# callisto_schematics_analog.net
KiCad netlist of a schematic drawn in Altium Designer
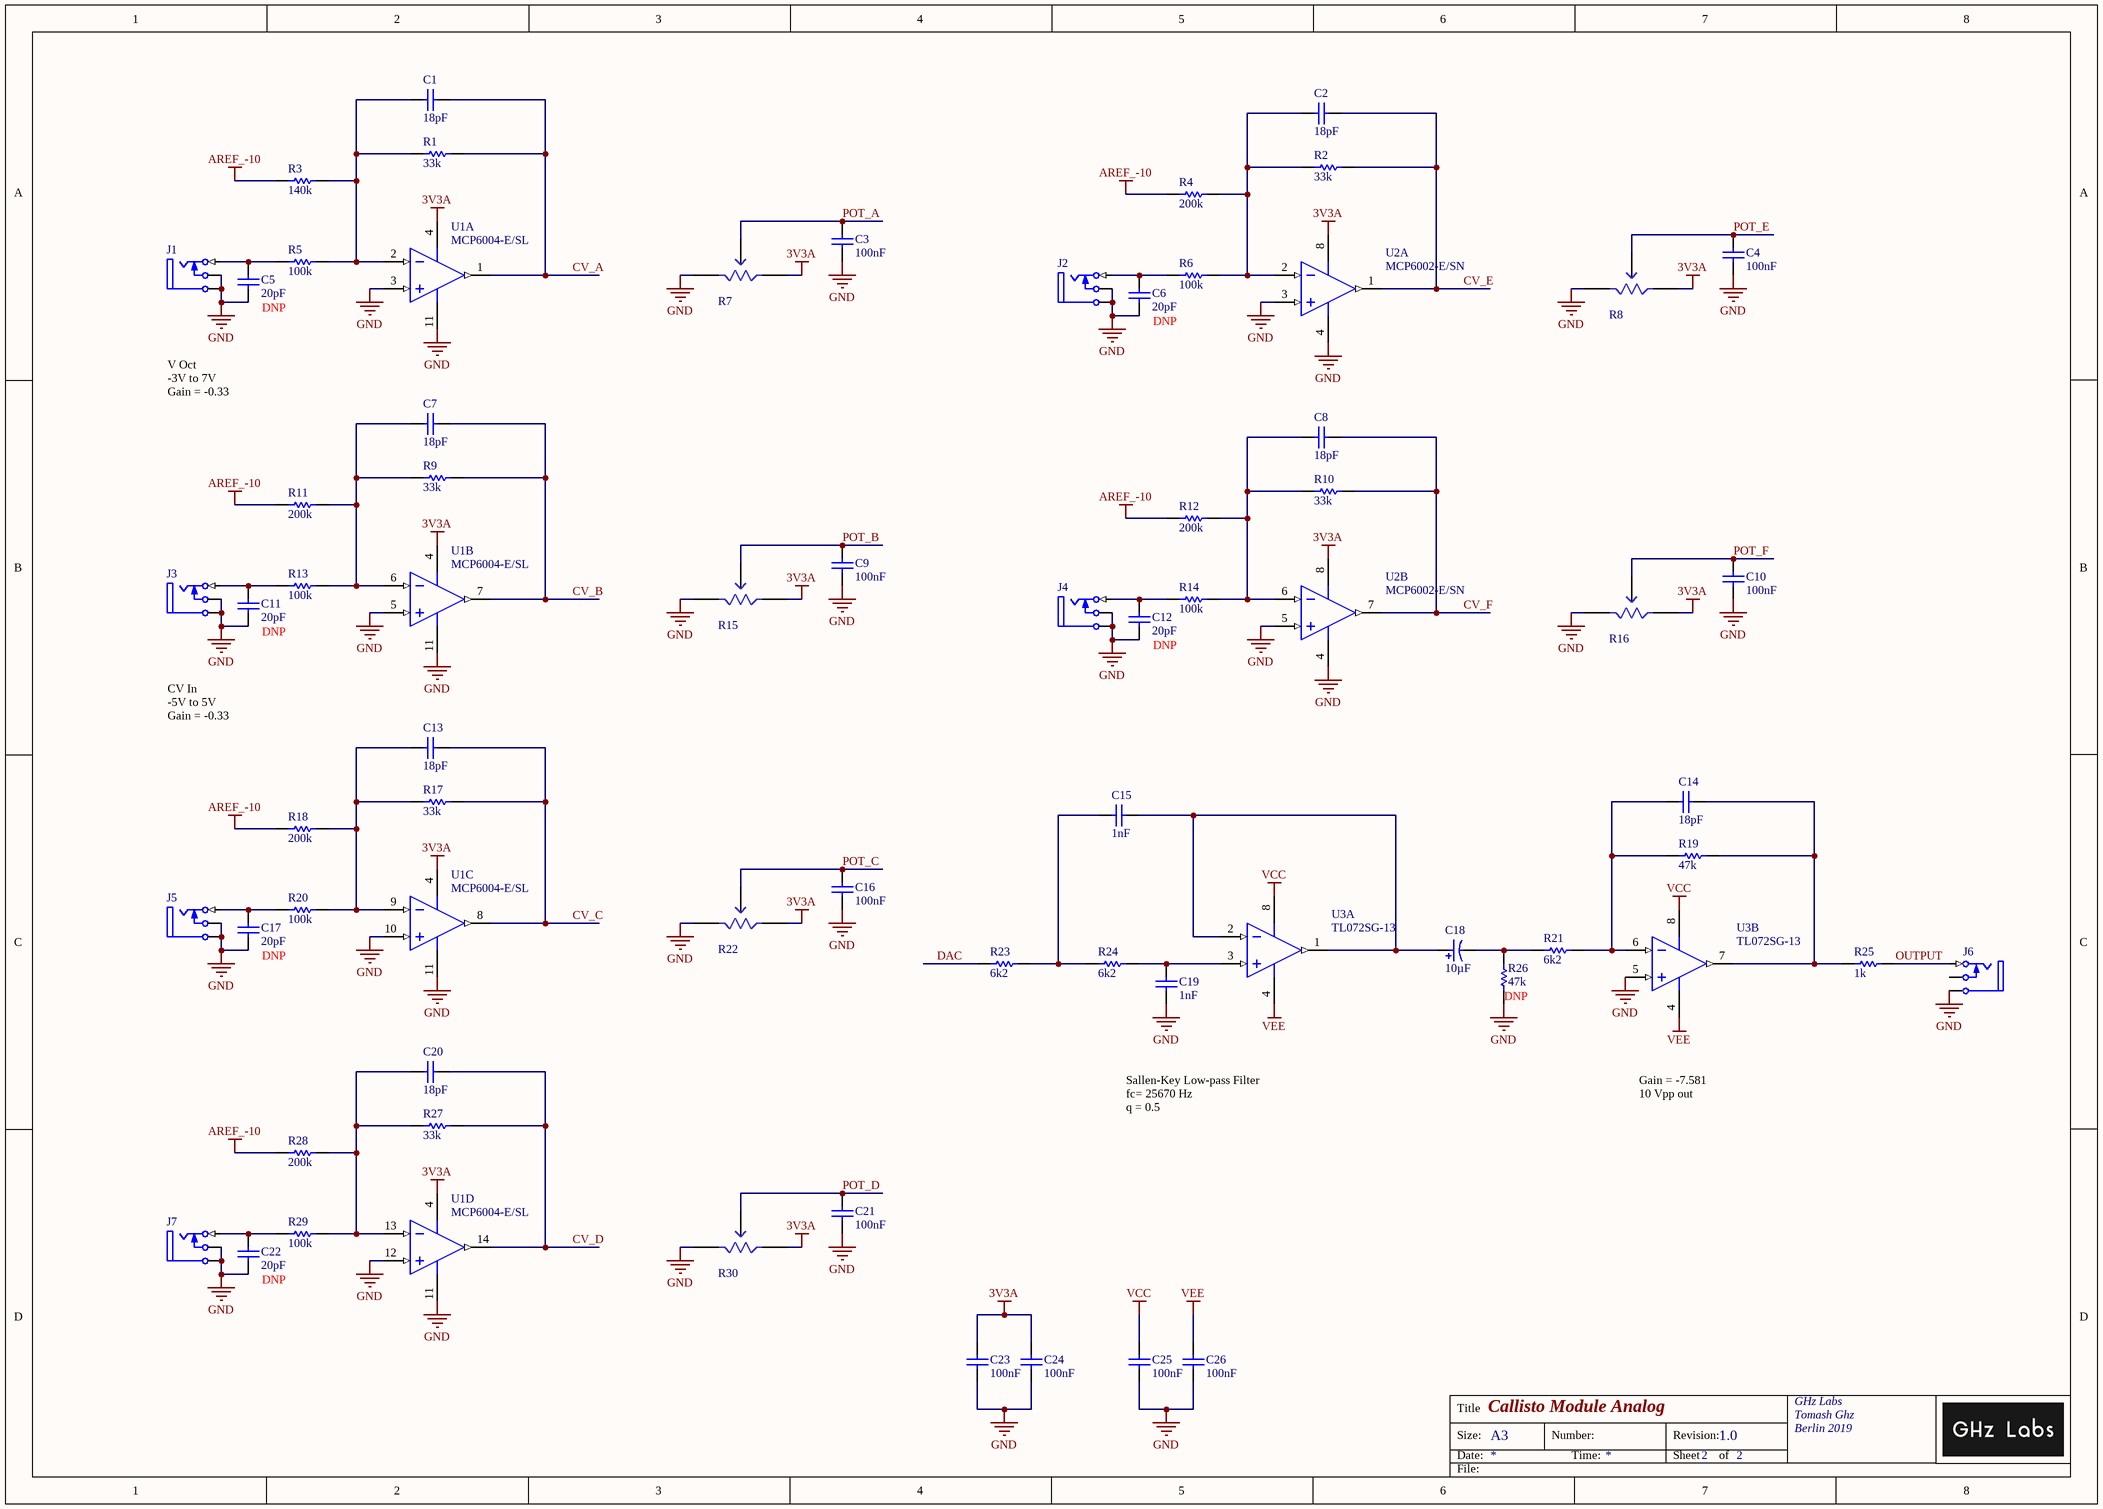
[diagram p0: callisto_schematics_analog.SchDoc]

(export (version "E")
  (design (tool "Eeschema 10.0.6"))
  (components
    (comp (ref "C1")
      (value "18pF")
      (footprint "GHzLabs_Parts:CAPA_0805")
      (description "Capacitor")
      (fields
        (field (name "PARTNUMBER") "C0805C180J5GAC7210")
        (field (name "MANUFACTURER") "KEMET")
        (field (name "PUBLISHER") "Altium Limited")
      )
      (libsource (lib "GHzLabs_Parts") (part "Cap"))
    )
    (comp (ref "C2")
      (value "18pF")
      (footprint "GHzLabs_Parts:CAPA_0805")
      (description "Capacitor")
      (fields
        (field (name "PARTNUMBER") "C0805C180J5GAC7210")
        (field (name "MANUFACTURER") "KEMET")
        (field (name "PUBLISHER") "Altium Limited")
      )
      (libsource (lib "GHzLabs_Parts") (part "Cap"))
    )
    (comp (ref "C3")
      (value "100nF")
      (footprint "GHzLabs_Parts:CAPA_0805")
      (description "Capacitor")
      (fields
        (field (name "MANUFACTURER") "KEMET")
        (field (name "PARTNUMBER") "C0805C104K4RAC")
        (field (name "PUBLISHER") "Altium Limited")
      )
      (libsource (lib "Miscellaneous Devices") (part "Cap"))
    )
    (comp (ref "C4")
      (value "100nF")
      (footprint "GHzLabs_Parts:CAPA_0805")
      (description "Capacitor")
      (fields
        (field (name "MANUFACTURER") "KEMET")
        (field (name "PARTNUMBER") "C0805C104K4RAC")
        (field (name "PUBLISHER") "Altium Limited")
      )
      (libsource (lib "Miscellaneous Devices") (part "Cap"))
    )
    (comp (ref "C5")
      (value "20pF")
      (footprint "GHzLabs_Parts:CAPA_0805")
      (description "Capacitor")
      (fields (field (name "PUBLISHER") "Altium Limited"))
      (libsource (lib "GHzLabs_Parts") (part "Cap"))
    )
    (comp (ref "C6")
      (value "20pF")
      (footprint "GHzLabs_Parts:CAPA_0805")
      (description "Capacitor")
      (fields (field (name "PUBLISHER") "Altium Limited"))
      (libsource (lib "GHzLabs_Parts") (part "Cap"))
    )
    (comp (ref "C7")
      (value "18pF")
      (footprint "GHzLabs_Parts:CAPA_0805")
      (description "Capacitor")
      (fields
        (field (name "PARTNUMBER") "C0805C180J5GAC7210")
        (field (name "MANUFACTURER") "KEMET")
        (field (name "PUBLISHER") "Altium Limited")
      )
      (libsource (lib "GHzLabs_Parts") (part "Cap"))
    )
    (comp (ref "C8")
      (value "18pF")
      (footprint "GHzLabs_Parts:CAPA_0805")
      (description "Capacitor")
      (fields
        (field (name "PARTNUMBER") "C0805C180J5GAC7210")
        (field (name "MANUFACTURER") "KEMET")
        (field (name "PUBLISHER") "Altium Limited")
      )
      (libsource (lib "GHzLabs_Parts") (part "Cap"))
    )
    (comp (ref "C9")
      (value "100nF")
      (footprint "GHzLabs_Parts:CAPA_0805")
      (description "Capacitor")
      (fields
        (field (name "MANUFACTURER") "KEMET")
        (field (name "PARTNUMBER") "C0805C104K4RAC")
        (field (name "PUBLISHER") "Altium Limited")
      )
      (libsource (lib "Miscellaneous Devices") (part "Cap"))
    )
    (comp (ref "C10")
      (value "100nF")
      (footprint "GHzLabs_Parts:CAPA_0805")
      (description "Capacitor")
      (fields
        (field (name "MANUFACTURER") "KEMET")
        (field (name "PARTNUMBER") "C0805C104K4RAC")
        (field (name "PUBLISHER") "Altium Limited")
      )
      (libsource (lib "Miscellaneous Devices") (part "Cap"))
    )
    (comp (ref "C11")
      (value "20pF")
      (footprint "GHzLabs_Parts:CAPA_0805")
      (description "Capacitor")
      (fields (field (name "PUBLISHER") "Altium Limited"))
      (libsource (lib "GHzLabs_Parts") (part "Cap"))
    )
    (comp (ref "C12")
      (value "20pF")
      (footprint "GHzLabs_Parts:CAPA_0805")
      (description "Capacitor")
      (fields (field (name "PUBLISHER") "Altium Limited"))
      (libsource (lib "GHzLabs_Parts") (part "Cap"))
    )
    (comp (ref "C13")
      (value "18pF")
      (footprint "GHzLabs_Parts:CAPA_0805")
      (description "Capacitor")
      (fields
        (field (name "PARTNUMBER") "C0805C180J5GAC7210")
        (field (name "MANUFACTURER") "KEMET")
        (field (name "PUBLISHER") "Altium Limited")
      )
      (libsource (lib "GHzLabs_Parts") (part "Cap"))
    )
    (comp (ref "C14")
      (value "18pF")
      (footprint "GHzLabs_Parts:CAPA_0805")
      (description "Capacitor")
      (fields
        (field (name "PARTNUMBER") "C0805C180J5GAC7210")
        (field (name "MANUFACTURER") "KEMET")
        (field (name "PUBLISHER") "Altium Limited")
      )
      (libsource (lib "GHzLabs_Parts") (part "Cap"))
    )
    (comp (ref "C15")
      (value "1nF")
      (footprint "GHzLabs_Parts:CAPA_0805")
      (description "Capacitor")
      (fields
        (field (name "PARTNUMBER") "C0805C102K5GAC")
        (field (name "MANUFACTURER") "KEMET")
        (field (name "PUBLISHER") "Altium Limited")
      )
      (libsource (lib "GHzLabs_Parts") (part "Cap"))
    )
    (comp (ref "C16")
      (value "100nF")
      (footprint "GHzLabs_Parts:CAPA_0805")
      (description "Capacitor")
      (fields
        (field (name "MANUFACTURER") "KEMET")
        (field (name "PARTNUMBER") "C0805C104K4RAC")
        (field (name "PUBLISHER") "Altium Limited")
      )
      (libsource (lib "Miscellaneous Devices") (part "Cap"))
    )
    (comp (ref "C17")
      (value "20pF")
      (footprint "GHzLabs_Parts:CAPA_0805")
      (description "Capacitor")
      (fields (field (name "PUBLISHER") "Altium Limited"))
      (libsource (lib "GHzLabs_Parts") (part "Cap"))
    )
    (comp (ref "C18")
      (value "10uF Electrolytic Capacitor")
      (footprint "PNSC-FK-V-B_V")
      (fields
        (field (name "MANUFACTURER") "Panasonic")
        (field (name "CAPACITANCE") "10µF")
        (field (name "PARTNUMBER") "EEE-FK1E100R")
      )
      (libsource (lib "Altium Content Vault") (part "CMP-2000-06211-1"))
    )
    (comp (ref "C19")
      (value "1nF")
      (footprint "GHzLabs_Parts:CAPA_0805")
      (description "Capacitor")
      (fields
        (field (name "PARTNUMBER") "C0805C102K5GAC")
        (field (name "MANUFACTURER") "KEMET")
        (field (name "PUBLISHER") "Altium Limited")
      )
      (libsource (lib "GHzLabs_Parts") (part "Cap"))
    )
    (comp (ref "C20")
      (value "18pF")
      (footprint "GHzLabs_Parts:CAPA_0805")
      (description "Capacitor")
      (fields
        (field (name "PARTNUMBER") "C0805C180J5GAC7210")
        (field (name "MANUFACTURER") "KEMET")
        (field (name "PUBLISHER") "Altium Limited")
      )
      (libsource (lib "GHzLabs_Parts") (part "Cap"))
    )
    (comp (ref "C21")
      (value "100nF")
      (footprint "GHzLabs_Parts:CAPA_0805")
      (description "Capacitor")
      (fields
        (field (name "MANUFACTURER") "KEMET")
        (field (name "PARTNUMBER") "C0805C104K4RAC")
        (field (name "PUBLISHER") "Altium Limited")
      )
      (libsource (lib "Miscellaneous Devices") (part "Cap"))
    )
    (comp (ref "C22")
      (value "20pF")
      (footprint "GHzLabs_Parts:CAPA_0805")
      (description "Capacitor")
      (fields (field (name "PUBLISHER") "Altium Limited"))
      (libsource (lib "GHzLabs_Parts") (part "Cap"))
    )
    (comp (ref "C23")
      (value "100nF")
      (footprint "GHzLabs_Parts:CAPA_0805")
      (description "Capacitor")
      (fields
        (field (name "MANUFACTURER") "KEMET")
        (field (name "PARTNUMBER") "C0805C104K4RAC")
        (field (name "PUBLISHER") "Altium Limited")
      )
      (libsource (lib "Miscellaneous Devices") (part "Cap"))
    )
    (comp (ref "C24")
      (value "100nF")
      (footprint "GHzLabs_Parts:CAPA_0805")
      (description "Capacitor")
      (fields
        (field (name "MANUFACTURER") "KEMET")
        (field (name "PARTNUMBER") "C0805C104K4RAC")
        (field (name "PUBLISHER") "Altium Limited")
      )
      (libsource (lib "Miscellaneous Devices") (part "Cap"))
    )
    (comp (ref "C25")
      (value "100nF")
      (footprint "GHzLabs_Parts:CAPA_0805")
      (description "Capacitor")
      (fields
        (field (name "MANUFACTURER") "KEMET")
        (field (name "PARTNUMBER") "C0805C104K4RAC")
        (field (name "PUBLISHER") "Altium Limited")
      )
      (libsource (lib "Miscellaneous Devices") (part "Cap"))
    )
    (comp (ref "C26")
      (value "100nF")
      (footprint "GHzLabs_Parts:CAPA_0805")
      (description "Capacitor")
      (fields
        (field (name "MANUFACTURER") "KEMET")
        (field (name "PARTNUMBER") "C0805C104K4RAC")
        (field (name "PUBLISHER") "Altium Limited")
      )
      (libsource (lib "Miscellaneous Devices") (part "Cap"))
    )
    (comp (ref "J1")
      (value "Phonejack2 TN")
      (footprint "GHzLabs_Parts:Thonkiconn")
      (description "Jack Socket")
      (fields (field (name "PART") "ACJM-MV35-2S") (field (name "MANUFACTURER") "Thonk"))
      (libsource (lib "GHzLabs_Parts") (part "Phonejack2 TN"))
    )
    (comp (ref "J2")
      (value "Phonejack2 TN")
      (footprint "GHzLabs_Parts:Thonkiconn")
      (description "Jack Socket")
      (fields (field (name "PART") "ACJM-MV35-2S") (field (name "MANUFACTURER") "Thonk"))
      (libsource (lib "GHzLabs_Parts") (part "Phonejack2 TN"))
    )
    (comp (ref "J3")
      (value "Phonejack2 TN")
      (footprint "GHzLabs_Parts:Thonkiconn")
      (description "Jack Socket")
      (fields (field (name "PART") "ACJM-MV35-2S") (field (name "MANUFACTURER") "Thonk"))
      (libsource (lib "GHzLabs_Parts") (part "Phonejack2 TN"))
    )
    (comp (ref "J4")
      (value "Phonejack2 TN")
      (footprint "GHzLabs_Parts:Thonkiconn")
      (description "Jack Socket")
      (fields (field (name "PART") "ACJM-MV35-2S") (field (name "MANUFACTURER") "Thonk"))
      (libsource (lib "GHzLabs_Parts") (part "Phonejack2 TN"))
    )
    (comp (ref "J5")
      (value "Phonejack2 TN")
      (footprint "GHzLabs_Parts:Thonkiconn")
      (description "Jack Socket")
      (fields (field (name "PART") "ACJM-MV35-2S") (field (name "MANUFACTURER") "Thonk"))
      (libsource (lib "GHzLabs_Parts") (part "Phonejack2 TN"))
    )
    (comp (ref "J6")
      (value "Phonejack2 TN")
      (footprint "GHzLabs_Parts:Thonkiconn")
      (description "Jack Socket")
      (fields (field (name "PART") "ACJM-MV35-2S") (field (name "MANUFACTURER") "Thonk"))
      (libsource (lib "GHzLabs_Parts") (part "Phonejack2 TN"))
    )
    (comp (ref "J7")
      (value "Phonejack2 TN")
      (footprint "GHzLabs_Parts:Thonkiconn")
      (description "Jack Socket")
      (fields (field (name "PART") "ACJM-MV35-2S") (field (name "MANUFACTURER") "Thonk"))
      (libsource (lib "GHzLabs_Parts") (part "Phonejack2 TN"))
    )
    (comp (ref "R1")
      (value "33k")
      (footprint "GHzLabs_Parts:RES_0805")
      (description "33k 0805")
      (fields (field (name "PARTNUMBER") "RR1220P-333-D") (field (name "MANUFACTURER") "Susumu"))
      (libsource (lib "GHzLabs_Parts") (part "Resistor"))
    )
    (comp (ref "R2")
      (value "33k")
      (footprint "GHzLabs_Parts:RES_0805")
      (description "33k 0805")
      (fields (field (name "PARTNUMBER") "RR1220P-333-D") (field (name "MANUFACTURER") "Susumu"))
      (libsource (lib "GHzLabs_Parts") (part "Resistor"))
    )
    (comp (ref "R3")
      (value "140k")
      (footprint "GHzLabs_Parts:RES_0805")
      (description "140k 0805")
      (fields (field (name "PARTNUMBER") "RR1220P-1403-D-M") (field (name "MANUFACTURER") "Susumu"))
      (libsource (lib "GHzLabs_Parts") (part "Resistor"))
    )
    (comp (ref "R4")
      (value "200k")
      (footprint "GHzLabs_Parts:RES_0805")
      (description "200k 0805")
      (fields (field (name "PARTNUMBER") "RR1220P-204-D") (field (name "MANUFACTURER") "Susumu"))
      (libsource (lib "GHzLabs_Parts") (part "Resistor"))
    )
    (comp (ref "R5")
      (value "100k")
      (footprint "GHzLabs_Parts:RES_0805")
      (description "100k 0805")
      (fields (field (name "PARTNUMBER") "RR1220P-104-D") (field (name "MANUFACTURER") "Susumu"))
      (libsource (lib "GHzLabs_Parts") (part "Resistor"))
    )
    (comp (ref "R6")
      (value "100k")
      (footprint "GHzLabs_Parts:RES_0805")
      (description "100k 0805")
      (fields (field (name "PARTNUMBER") "RR1220P-104-D") (field (name "MANUFACTURER") "Susumu"))
      (libsource (lib "GHzLabs_Parts") (part "Resistor"))
    )
    (comp (ref "R7")
      (value "Thumb Potentiometer")
      (footprint "GHzLabs_Parts:POT-Thumb")
      (fields (field (name "PARTNUMBER") "PTV09A-4020U-B104") (field (name "MANUFACTURER") "Bourns"))
      (libsource (lib "myParts") (part "Potentiometer"))
    )
    (comp (ref "R8")
      (value "Thumb Potentiometer")
      (footprint "GHzLabs_Parts:POT-Thumb")
      (fields (field (name "PARTNUMBER") "PTV09A-4020U-B104") (field (name "MANUFACTURER") "Bourns"))
      (libsource (lib "myParts") (part "Potentiometer"))
    )
    (comp (ref "R9")
      (value "33k")
      (footprint "GHzLabs_Parts:RES_0805")
      (description "33k 0805")
      (fields (field (name "PARTNUMBER") "RR1220P-333-D") (field (name "MANUFACTURER") "Susumu"))
      (libsource (lib "GHzLabs_Parts") (part "Resistor"))
    )
    (comp (ref "R10")
      (value "33k")
      (footprint "GHzLabs_Parts:RES_0805")
      (description "33k 0805")
      (fields (field (name "PARTNUMBER") "RR1220P-333-D") (field (name "MANUFACTURER") "Susumu"))
      (libsource (lib "GHzLabs_Parts") (part "Resistor"))
    )
    (comp (ref "R11")
      (value "200k")
      (footprint "GHzLabs_Parts:RES_0805")
      (description "200k 0805")
      (fields (field (name "PARTNUMBER") "RR1220P-204-D") (field (name "MANUFACTURER") "Susumu"))
      (libsource (lib "GHzLabs_Parts") (part "Resistor"))
    )
    (comp (ref "R12")
      (value "200k")
      (footprint "GHzLabs_Parts:RES_0805")
      (description "200k 0805")
      (fields (field (name "PARTNUMBER") "RR1220P-204-D") (field (name "MANUFACTURER") "Susumu"))
      (libsource (lib "GHzLabs_Parts") (part "Resistor"))
    )
    (comp (ref "R13")
      (value "100k")
      (footprint "GHzLabs_Parts:RES_0805")
      (description "100k 0805")
      (fields (field (name "PARTNUMBER") "RR1220P-104-D") (field (name "MANUFACTURER") "Susumu"))
      (libsource (lib "GHzLabs_Parts") (part "Resistor"))
    )
    (comp (ref "R14")
      (value "100k")
      (footprint "GHzLabs_Parts:RES_0805")
      (description "100k 0805")
      (fields (field (name "PARTNUMBER") "RR1220P-104-D") (field (name "MANUFACTURER") "Susumu"))
      (libsource (lib "GHzLabs_Parts") (part "Resistor"))
    )
    (comp (ref "R15")
      (value "Thumb Potentiometer")
      (footprint "GHzLabs_Parts:POT-Thumb")
      (fields (field (name "PARTNUMBER") "PTV09A-4020U-B104") (field (name "MANUFACTURER") "Bourns"))
      (libsource (lib "myParts") (part "Potentiometer"))
    )
    (comp (ref "R16")
      (value "Potentiometer")
      (footprint "GHzLabs_Parts:POT-ALPHA")
      (fields (field (name "PARTNUMBER") "P0915N-FC15BR100K") (field (name "MANUFACTURER") "TT Electronics"))
      (libsource (lib "myParts") (part "Potentiometer"))
    )
    (comp (ref "R17")
      (value "33k")
      (footprint "GHzLabs_Parts:RES_0805")
      (description "33k 0805")
      (fields (field (name "PARTNUMBER") "RR1220P-333-D") (field (name "MANUFACTURER") "Susumu"))
      (libsource (lib "GHzLabs_Parts") (part "Resistor"))
    )
    (comp (ref "R18")
      (value "200k")
      (footprint "GHzLabs_Parts:RES_0805")
      (description "200k 0805")
      (fields (field (name "PARTNUMBER") "RR1220P-204-D") (field (name "MANUFACTURER") "Susumu"))
      (libsource (lib "GHzLabs_Parts") (part "Resistor"))
    )
    (comp (ref "R19")
      (value "47k")
      (footprint "GHzLabs_Parts:RES_0805")
      (description "47k 0805")
      (fields (field (name "PARTNUMBER") "RT0805FRE0747KL") (field (name "MANUFACTURER") "Yageo"))
      (libsource (lib "GHzLabs_Parts") (part "Resistor"))
    )
    (comp (ref "R20")
      (value "100k")
      (footprint "GHzLabs_Parts:RES_0805")
      (description "100k 0805")
      (fields (field (name "PARTNUMBER") "RR1220P-104-D") (field (name "MANUFACTURER") "Susumu"))
      (libsource (lib "GHzLabs_Parts") (part "Resistor"))
    )
    (comp (ref "R21")
      (value "6k2")
      (footprint "GHzLabs_Parts:RES_0805")
      (description "6k2 0805")
      (fields (field (name "PARTNUMBER") "RT0805FRE076K2L") (field (name "MANUFACTURER") "Yageo"))
      (libsource (lib "GHzLabs_Parts") (part "Resistor"))
    )
    (comp (ref "R22")
      (value "Potentiometer")
      (footprint "GHzLabs_Parts:POT-ALPHA")
      (fields (field (name "PARTNUMBER") "P0915N-FC15BR100K") (field (name "MANUFACTURER") "TT Electronics"))
      (libsource (lib "myParts") (part "Potentiometer"))
    )
    (comp (ref "R23")
      (value "6k2")
      (footprint "GHzLabs_Parts:RES_0805")
      (description "6k2 0805")
      (fields (field (name "PARTNUMBER") "RT0805FRE076K2L") (field (name "MANUFACTURER") "Yageo"))
      (libsource (lib "GHzLabs_Parts") (part "Resistor"))
    )
    (comp (ref "R24")
      (value "6k2")
      (footprint "GHzLabs_Parts:RES_0805")
      (description "6k2 0805")
      (fields (field (name "PARTNUMBER") "RT0805FRE076K2L") (field (name "MANUFACTURER") "Yageo"))
      (libsource (lib "GHzLabs_Parts") (part "Resistor"))
    )
    (comp (ref "R25")
      (value "1k")
      (footprint "GHzLabs_Parts:RES_0805")
      (description "1k 0805")
      (fields (field (name "PARTNUMBER") "RR1220P-102-D") (field (name "MANUFACTURER") "Susumu"))
      (libsource (lib "GHzLabs_Parts") (part "Resistor"))
    )
    (comp (ref "R26")
      (value "47k")
      (footprint "GHzLabs_Parts:RES_0805")
      (description "47k 0805")
      (fields (field (name "PARTNUMBER") "RT0805FRE0747KL") (field (name "MANUFACTURER") "Yageo"))
      (libsource (lib "GHzLabs_Parts") (part "Resistor"))
    )
    (comp (ref "R27")
      (value "33k")
      (footprint "GHzLabs_Parts:RES_0805")
      (description "33k 0805")
      (fields (field (name "PARTNUMBER") "RR1220P-333-D") (field (name "MANUFACTURER") "Susumu"))
      (libsource (lib "GHzLabs_Parts") (part "Resistor"))
    )
    (comp (ref "R28")
      (value "200k")
      (footprint "GHzLabs_Parts:RES_0805")
      (description "200k 0805")
      (fields (field (name "PARTNUMBER") "RR1220P-204-D") (field (name "MANUFACTURER") "Susumu"))
      (libsource (lib "GHzLabs_Parts") (part "Resistor"))
    )
    (comp (ref "R29")
      (value "100k")
      (footprint "GHzLabs_Parts:RES_0805")
      (description "100k 0805")
      (fields (field (name "PARTNUMBER") "RR1220P-104-D") (field (name "MANUFACTURER") "Susumu"))
      (libsource (lib "GHzLabs_Parts") (part "Resistor"))
    )
    (comp (ref "R30")
      (value "Potentiometer")
      (footprint "GHzLabs_Parts:POT-ALPHA")
      (fields (field (name "PARTNUMBER") "P0915N-FC15BR100K") (field (name "MANUFACTURER") "TT Electronics"))
      (libsource (lib "myParts") (part "Potentiometer"))
    )
    (comp (ref "U1")
      (value "MCP6004-E/SL")
      (footprint "SOIC-SL14_M")
      (description "1 MHz, Low-Power Operational Amplifier, 14-Pin SOIC, Extended Temperature")
      (fields
        (field (name "PARTNUMBER") "MCP6004T-E/SL")
        (field (name "MANUFACTURER") "Microchip Technology")
        (field (name "PUBLISHER") "Altium Limited")
      )
      (libsource (lib "Microchip Linear Devices") (part "MCP6004-E/SL"))
    )
    (comp (ref "U2")
      (value "MCP6002-E/SN")
      (footprint "SOIC-SN8_M")
      (description "1 MHz, Low-Power Operational Amplifier, 8-Pin SOIC, Extended Temperature")
      (fields (field (name "MANUFACTURER") "Microchip Technology"))
      (libsource (lib "Altium Content Vault") (part "CMP-0187-00368-2"))
    )
    (comp (ref "U3")
      (value "TL072SG-13")
      (footprint "D0008A_M")
      (fields (field (name "MANUFACTURER") "Diodes Incorporated"))
      (libsource (lib "Altium Content Vault") (part "CMP-0015-00092-2"))
    )
  )
  (nets
    (net (code "1") (name "/CV_A") (class "Default")
      (node (ref "C1") (pin "2") (pinfunction "2_2") (pintype "passive"))
      (node (ref "R1") (pin "1") (pinfunction "1_1") (pintype "passive"))
      (node (ref "U1") (pin "1") (pinfunction "VOUTA_1") (pintype "output"))
    )
    (net (code "2") (name "/CV_B") (class "Default")
      (node (ref "C7") (pin "2") (pinfunction "2_2") (pintype "passive"))
      (node (ref "R9") (pin "1") (pinfunction "1_1") (pintype "passive"))
      (node (ref "U1") (pin "7") (pinfunction "VOUTB_7") (pintype "output"))
    )
    (net (code "3") (name "/CV_C") (class "Default")
      (node (ref "C13") (pin "2") (pinfunction "2_2") (pintype "passive"))
      (node (ref "R17") (pin "1") (pinfunction "1_1") (pintype "passive"))
      (node (ref "U1") (pin "8") (pinfunction "VOUTC_8") (pintype "output"))
    )
    (net (code "4") (name "/CV_D") (class "Default")
      (node (ref "C20") (pin "2") (pinfunction "2_2") (pintype "passive"))
      (node (ref "R27") (pin "1") (pinfunction "1_1") (pintype "passive"))
      (node (ref "U1") (pin "14") (pinfunction "VOUTD_14") (pintype "output"))
    )
    (net (code "5") (name "/CV_E") (class "Default")
      (node (ref "C2") (pin "2") (pinfunction "2_2") (pintype "passive"))
      (node (ref "R2") (pin "1") (pinfunction "1_1") (pintype "passive"))
      (node (ref "U2") (pin "1") (pinfunction "VOUTA_1") (pintype "output"))
    )
    (net (code "6") (name "/CV_F") (class "Default")
      (node (ref "C8") (pin "2") (pinfunction "2_2") (pintype "passive"))
      (node (ref "R10") (pin "1") (pinfunction "1_1") (pintype "passive"))
      (node (ref "U2") (pin "7") (pinfunction "VOUTB_7") (pintype "output"))
    )
    (net (code "7") (name "/DAC") (class "Default")
      (node (ref "R23") (pin "2") (pinfunction "2_2") (pintype "passive"))
    )
    (net (code "8") (name "/OUTPUT") (class "Default")
      (node (ref "J6") (pin "1") (pinfunction "T_1") (pintype "input"))
      (node (ref "R25") (pin "1") (pinfunction "1_1") (pintype "passive"))
    )
    (net (code "9") (name "/POT_A") (class "Default")
      (node (ref "C3") (pin "1") (pinfunction "1_1") (pintype "passive"))
      (node (ref "R7") (pin "2") (pinfunction "2_2") (pintype "power_in"))
    )
    (net (code "10") (name "/POT_B") (class "Default")
      (node (ref "C9") (pin "1") (pinfunction "1_1") (pintype "passive"))
      (node (ref "R15") (pin "2") (pinfunction "2_2") (pintype "power_in"))
    )
    (net (code "11") (name "/POT_C") (class "Default")
      (node (ref "C16") (pin "1") (pinfunction "1_1") (pintype "passive"))
      (node (ref "R22") (pin "2") (pinfunction "2_2") (pintype "power_in"))
    )
    (net (code "12") (name "/POT_D") (class "Default")
      (node (ref "C21") (pin "1") (pinfunction "1_1") (pintype "passive"))
      (node (ref "R30") (pin "2") (pinfunction "2_2") (pintype "power_in"))
    )
    (net (code "13") (name "/POT_E") (class "Default")
      (node (ref "C4") (pin "1") (pinfunction "1_1") (pintype "passive"))
      (node (ref "R8") (pin "2") (pinfunction "2_2") (pintype "power_in"))
    )
    (net (code "14") (name "/POT_F") (class "Default")
      (node (ref "C10") (pin "1") (pinfunction "1_1") (pintype "passive"))
      (node (ref "R16") (pin "2") (pinfunction "2_2") (pintype "power_in"))
    )
    (net (code "15") (name "3V3A") (class "Default")
      (node (ref "C23") (pin "1") (pinfunction "1_1") (pintype "passive"))
      (node (ref "C24") (pin "1") (pinfunction "1_1") (pintype "passive"))
      (node (ref "R15") (pin "3") (pinfunction "3_3") (pintype "power_in"))
      (node (ref "R16") (pin "3") (pinfunction "3_3") (pintype "power_in"))
      (node (ref "R22") (pin "3") (pinfunction "3_3") (pintype "power_in"))
      (node (ref "R30") (pin "3") (pinfunction "3_3") (pintype "power_in"))
      (node (ref "R7") (pin "3") (pinfunction "3_3") (pintype "power_in"))
      (node (ref "R8") (pin "3") (pinfunction "3_3") (pintype "power_in"))
      (node (ref "U1") (pin "4") (pinfunction "VDD_4") (pintype "power_in"))
      (node (ref "U2") (pin "8") (pinfunction "VDD_8") (pintype "power_in"))
    )
    (net (code "16") (name "AREF_-10") (class "Default")
      (node (ref "R11") (pin "2") (pinfunction "2_2") (pintype "passive"))
      (node (ref "R12") (pin "2") (pinfunction "2_2") (pintype "passive"))
      (node (ref "R18") (pin "2") (pinfunction "2_2") (pintype "passive"))
      (node (ref "R28") (pin "2") (pinfunction "2_2") (pintype "passive"))
      (node (ref "R3") (pin "2") (pinfunction "2_2") (pintype "passive"))
      (node (ref "R4") (pin "2") (pinfunction "2_2") (pintype "passive"))
    )
    (net (code "17") (name "GND") (class "Default")
      (node (ref "C10") (pin "2") (pinfunction "2_2") (pintype "passive"))
      (node (ref "C11") (pin "1") (pinfunction "1_1") (pintype "passive"))
      (node (ref "C12") (pin "1") (pinfunction "1_1") (pintype "passive"))
      (node (ref "C16") (pin "2") (pinfunction "2_2") (pintype "passive"))
      (node (ref "C17") (pin "1") (pinfunction "1_1") (pintype "passive"))
      (node (ref "C19") (pin "1") (pinfunction "1_1") (pintype "passive"))
      (node (ref "C21") (pin "2") (pinfunction "2_2") (pintype "passive"))
      (node (ref "C22") (pin "1") (pinfunction "1_1") (pintype "passive"))
      (node (ref "C23") (pin "2") (pinfunction "2_2") (pintype "passive"))
      (node (ref "C24") (pin "2") (pinfunction "2_2") (pintype "passive"))
      (node (ref "C25") (pin "2") (pinfunction "2_2") (pintype "passive"))
      (node (ref "C26") (pin "2") (pinfunction "2_2") (pintype "passive"))
      (node (ref "C3") (pin "2") (pinfunction "2_2") (pintype "passive"))
      (node (ref "C4") (pin "2") (pinfunction "2_2") (pintype "passive"))
      (node (ref "C5") (pin "1") (pinfunction "1_1") (pintype "passive"))
      (node (ref "C6") (pin "1") (pinfunction "1_1") (pintype "passive"))
      (node (ref "C9") (pin "2") (pinfunction "2_2") (pintype "passive"))
      (node (ref "J1") (pin "2") (pinfunction "TN_2") (pintype "passive"))
      (node (ref "J1") (pin "5") (pinfunction "S_5") (pintype "power_in"))
      (node (ref "J2") (pin "2") (pinfunction "TN_2") (pintype "passive"))
      (node (ref "J2") (pin "5") (pinfunction "S_5") (pintype "power_in"))
      (node (ref "J3") (pin "2") (pinfunction "TN_2") (pintype "passive"))
      (node (ref "J3") (pin "5") (pinfunction "S_5") (pintype "power_in"))
      (node (ref "J4") (pin "2") (pinfunction "TN_2") (pintype "passive"))
      (node (ref "J4") (pin "5") (pinfunction "S_5") (pintype "power_in"))
      (node (ref "J5") (pin "2") (pinfunction "TN_2") (pintype "passive"))
      (node (ref "J5") (pin "5") (pinfunction "S_5") (pintype "power_in"))
      (node (ref "J6") (pin "5") (pinfunction "S_5") (pintype "power_in"))
      (node (ref "J7") (pin "2") (pinfunction "TN_2") (pintype "passive"))
      (node (ref "J7") (pin "5") (pinfunction "S_5") (pintype "power_in"))
      (node (ref "R15") (pin "1") (pinfunction "1_1") (pintype "power_in"))
      (node (ref "R16") (pin "1") (pinfunction "1_1") (pintype "power_in"))
      (node (ref "R22") (pin "1") (pinfunction "1_1") (pintype "power_in"))
      (node (ref "R26") (pin "2") (pinfunction "2_2") (pintype "passive"))
      (node (ref "R30") (pin "1") (pinfunction "1_1") (pintype "power_in"))
      (node (ref "R7") (pin "1") (pinfunction "1_1") (pintype "power_in"))
      (node (ref "R8") (pin "1") (pinfunction "1_1") (pintype "power_in"))
      (node (ref "U1") (pin "10") (pinfunction "VINC+_10") (pintype "input"))
      (node (ref "U1") (pin "11") (pinfunction "VSS_11") (pintype "power_in"))
      (node (ref "U1") (pin "12") (pinfunction "VIND+_12") (pintype "input"))
      (node (ref "U1") (pin "3") (pinfunction "VINA+_3") (pintype "input"))
      (node (ref "U1") (pin "5") (pinfunction "VINB+_5") (pintype "input"))
      (node (ref "U2") (pin "3") (pinfunction "VINA+_3") (pintype "input"))
      (node (ref "U2") (pin "4") (pinfunction "VSS_4") (pintype "power_in"))
      (node (ref "U2") (pin "5") (pinfunction "VINB+_5") (pintype "input"))
      (node (ref "U3") (pin "5") (pinfunction "IN2+_5") (pintype "input"))
    )
    (net (code "18") (name "Net-(C15-Pad1)") (class "Default")
      (node (ref "C15") (pin "1") (pinfunction "1_1") (pintype "passive"))
      (node (ref "R23") (pin "1") (pinfunction "1_1") (pintype "passive"))
      (node (ref "R24") (pin "2") (pinfunction "2_2") (pintype "passive"))
    )
    (net (code "19") (name "Net-(C18-Pad2)") (class "Default")
      (node (ref "C18") (pin "2") (pinfunction "2_2") (pintype "passive"))
      (node (ref "R21") (pin "2") (pinfunction "2_2") (pintype "passive"))
      (node (ref "R26") (pin "1") (pinfunction "1_1") (pintype "passive"))
    )
    (net (code "20") (name "Net-(J1-T)") (class "Default")
      (node (ref "C5") (pin "2") (pinfunction "2_2") (pintype "passive"))
      (node (ref "J1") (pin "1") (pinfunction "T_1") (pintype "input"))
      (node (ref "R5") (pin "2") (pinfunction "2_2") (pintype "passive"))
    )
    (net (code "21") (name "Net-(J2-T)") (class "Default")
      (node (ref "C6") (pin "2") (pinfunction "2_2") (pintype "passive"))
      (node (ref "J2") (pin "1") (pinfunction "T_1") (pintype "input"))
      (node (ref "R6") (pin "2") (pinfunction "2_2") (pintype "passive"))
    )
    (net (code "22") (name "Net-(J3-T)") (class "Default")
      (node (ref "C11") (pin "2") (pinfunction "2_2") (pintype "passive"))
      (node (ref "J3") (pin "1") (pinfunction "T_1") (pintype "input"))
      (node (ref "R13") (pin "2") (pinfunction "2_2") (pintype "passive"))
    )
    (net (code "23") (name "Net-(J4-T)") (class "Default")
      (node (ref "C12") (pin "2") (pinfunction "2_2") (pintype "passive"))
      (node (ref "J4") (pin "1") (pinfunction "T_1") (pintype "input"))
      (node (ref "R14") (pin "2") (pinfunction "2_2") (pintype "passive"))
    )
    (net (code "24") (name "Net-(J5-T)") (class "Default")
      (node (ref "C17") (pin "2") (pinfunction "2_2") (pintype "passive"))
      (node (ref "J5") (pin "1") (pinfunction "T_1") (pintype "input"))
      (node (ref "R20") (pin "2") (pinfunction "2_2") (pintype "passive"))
    )
    (net (code "25") (name "Net-(J7-T)") (class "Default")
      (node (ref "C22") (pin "2") (pinfunction "2_2") (pintype "passive"))
      (node (ref "J7") (pin "1") (pinfunction "T_1") (pintype "input"))
      (node (ref "R29") (pin "2") (pinfunction "2_2") (pintype "passive"))
    )
    (net (code "26") (name "Net-(U1A-VINA-)") (class "Default")
      (node (ref "C1") (pin "1") (pinfunction "1_1") (pintype "passive"))
      (node (ref "R1") (pin "2") (pinfunction "2_2") (pintype "passive"))
      (node (ref "R3") (pin "1") (pinfunction "1_1") (pintype "passive"))
      (node (ref "R5") (pin "1") (pinfunction "1_1") (pintype "passive"))
      (node (ref "U1") (pin "2") (pinfunction "VINA-_2") (pintype "input"))
    )
    (net (code "27") (name "Net-(U1B-VINB-)") (class "Default")
      (node (ref "C7") (pin "1") (pinfunction "1_1") (pintype "passive"))
      (node (ref "R11") (pin "1") (pinfunction "1_1") (pintype "passive"))
      (node (ref "R13") (pin "1") (pinfunction "1_1") (pintype "passive"))
      (node (ref "R9") (pin "2") (pinfunction "2_2") (pintype "passive"))
      (node (ref "U1") (pin "6") (pinfunction "VINB-_6") (pintype "input"))
    )
    (net (code "28") (name "Net-(U1C-VINC-)") (class "Default")
      (node (ref "C13") (pin "1") (pinfunction "1_1") (pintype "passive"))
      (node (ref "R17") (pin "2") (pinfunction "2_2") (pintype "passive"))
      (node (ref "R18") (pin "1") (pinfunction "1_1") (pintype "passive"))
      (node (ref "R20") (pin "1") (pinfunction "1_1") (pintype "passive"))
      (node (ref "U1") (pin "9") (pinfunction "VINC-_9") (pintype "input"))
    )
    (net (code "29") (name "Net-(U1D-VIND-)") (class "Default")
      (node (ref "C20") (pin "1") (pinfunction "1_1") (pintype "passive"))
      (node (ref "R27") (pin "2") (pinfunction "2_2") (pintype "passive"))
      (node (ref "R28") (pin "1") (pinfunction "1_1") (pintype "passive"))
      (node (ref "R29") (pin "1") (pinfunction "1_1") (pintype "passive"))
      (node (ref "U1") (pin "13") (pinfunction "VIND-_13") (pintype "input"))
    )
    (net (code "30") (name "Net-(U2A-VINA-)") (class "Default")
      (node (ref "C2") (pin "1") (pinfunction "1_1") (pintype "passive"))
      (node (ref "R2") (pin "2") (pinfunction "2_2") (pintype "passive"))
      (node (ref "R4") (pin "1") (pinfunction "1_1") (pintype "passive"))
      (node (ref "R6") (pin "1") (pinfunction "1_1") (pintype "passive"))
      (node (ref "U2") (pin "2") (pinfunction "VINA-_2") (pintype "input"))
    )
    (net (code "31") (name "Net-(U2B-VINB-)") (class "Default")
      (node (ref "C8") (pin "1") (pinfunction "1_1") (pintype "passive"))
      (node (ref "R10") (pin "2") (pinfunction "2_2") (pintype "passive"))
      (node (ref "R12") (pin "1") (pinfunction "1_1") (pintype "passive"))
      (node (ref "R14") (pin "1") (pinfunction "1_1") (pintype "passive"))
      (node (ref "U2") (pin "6") (pinfunction "VINB-_6") (pintype "input"))
    )
    (net (code "32") (name "Net-(U3A-IN1+)") (class "Default")
      (node (ref "C19") (pin "2") (pinfunction "2_2") (pintype "passive"))
      (node (ref "R24") (pin "1") (pinfunction "1_1") (pintype "passive"))
      (node (ref "U3") (pin "3") (pinfunction "IN1+_3") (pintype "input"))
    )
    (net (code "33") (name "Net-(U3A-IN1-)") (class "Default")
      (node (ref "C15") (pin "2") (pinfunction "2_2") (pintype "passive"))
      (node (ref "C18") (pin "1") (pinfunction "1_1") (pintype "passive"))
      (node (ref "U3") (pin "1") (pinfunction "OUT1_1") (pintype "output"))
      (node (ref "U3") (pin "2") (pinfunction "IN1-_2") (pintype "input"))
    )
    (net (code "34") (name "Net-(U3B-IN2-)") (class "Default")
      (node (ref "C14") (pin "1") (pinfunction "1_1") (pintype "passive"))
      (node (ref "R19") (pin "2") (pinfunction "2_2") (pintype "passive"))
      (node (ref "R21") (pin "1") (pinfunction "1_1") (pintype "passive"))
      (node (ref "U3") (pin "6") (pinfunction "IN2-_6") (pintype "input"))
    )
    (net (code "35") (name "Net-(U3B-OUT2)") (class "Default")
      (node (ref "C14") (pin "2") (pinfunction "2_2") (pintype "passive"))
      (node (ref "R19") (pin "1") (pinfunction "1_1") (pintype "passive"))
      (node (ref "R25") (pin "2") (pinfunction "2_2") (pintype "passive"))
      (node (ref "U3") (pin "7") (pinfunction "OUT2_7") (pintype "output"))
    )
    (net (code "36") (name "VCC") (class "Default")
      (node (ref "C25") (pin "1") (pinfunction "1_1") (pintype "passive"))
      (node (ref "U3") (pin "8") (pinfunction "VCC+_8") (pintype "power_in"))
    )
    (net (code "37") (name "VEE") (class "Default")
      (node (ref "C26") (pin "1") (pinfunction "1_1") (pintype "passive"))
      (node (ref "U3") (pin "4") (pinfunction "VCC-_4") (pintype "power_in"))
    )
    (net (code "38") (name "unconnected-(J6-TN-Pad2)") (class "Default")
      (node (ref "J6") (pin "2") (pinfunction "TN_2") (pintype "passive"))
    )
  )
)
